# 388_Project.net
KiCad netlist of a schematic drawn in EAGLE
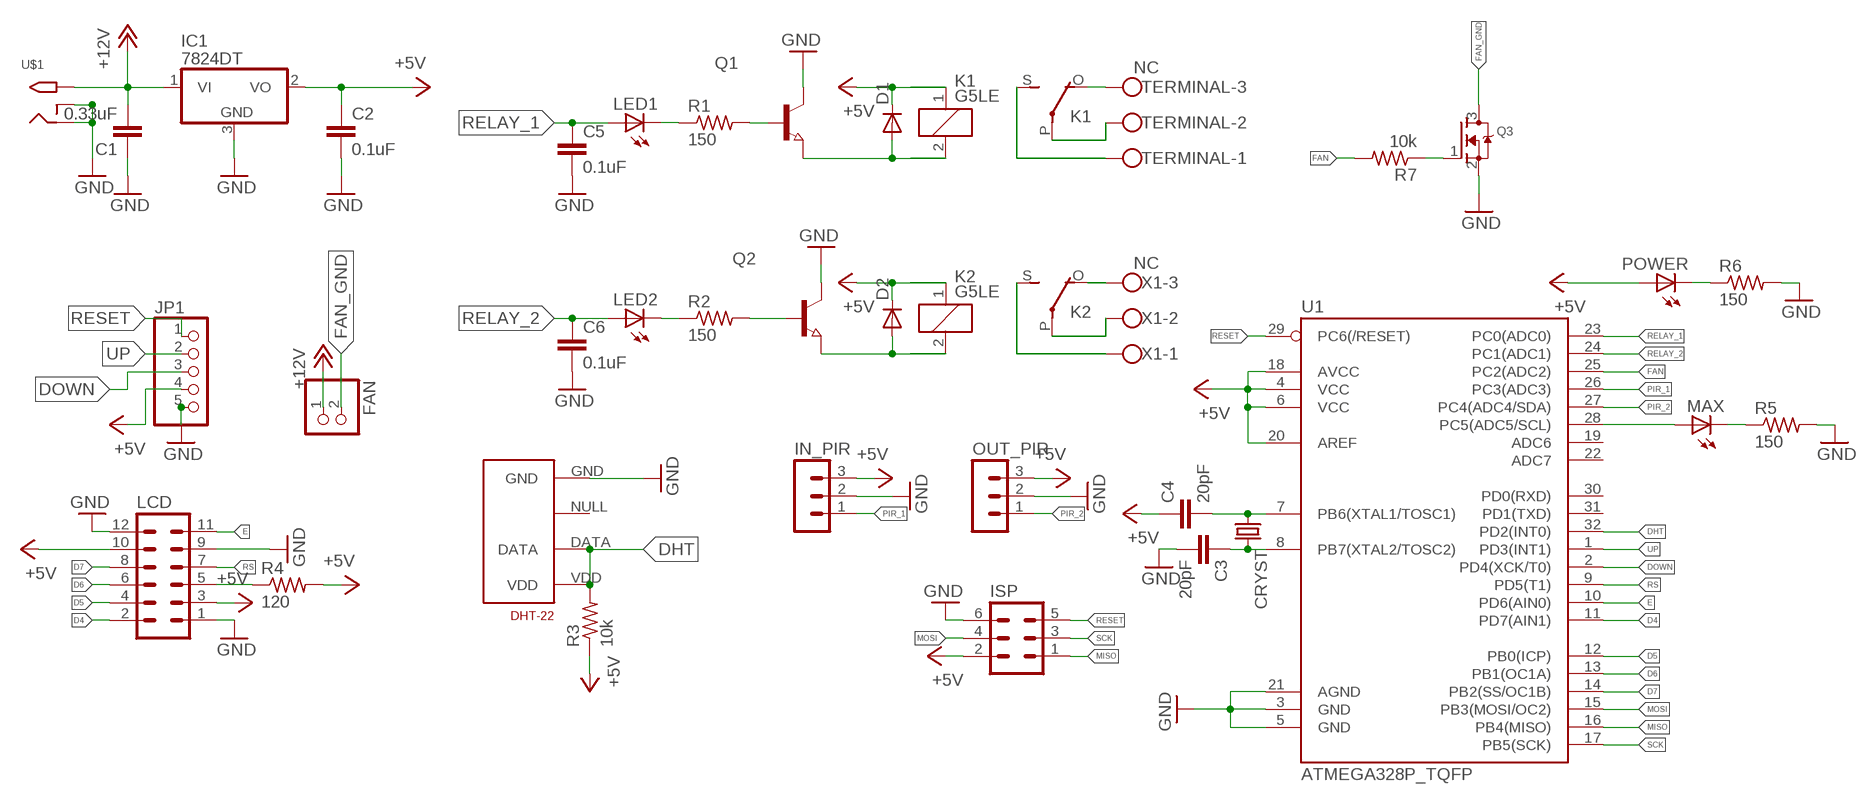
[diagram p0: schematic, sheet 1]

(export (version "E")
  (design (tool "Eeschema 10.0.6"))
  (components
    (comp (ref "C1")
      (value "0.33uF")
      (footprint "eagle-import:0805")
      (libsource (lib "eagle-import") (part "CAP0805"))
    )
    (comp (ref "C2")
      (value "0.1uF")
      (footprint "eagle-import:0805")
      (libsource (lib "eagle-import") (part "CAP0805"))
    )
    (comp (ref "C3")
      (value "20pF")
      (footprint "eagle-import:0805")
      (libsource (lib "eagle-import") (part "CAP0805"))
    )
    (comp (ref "C4")
      (value "20pF")
      (footprint "eagle-import:0805")
      (libsource (lib "eagle-import") (part "CAP0805"))
    )
    (comp (ref "C5")
      (value "0.1uF")
      (footprint "eagle-import:0805")
      (libsource (lib "eagle-import") (part "CAP0805"))
    )
    (comp (ref "C6")
      (value "0.1uF")
      (footprint "eagle-import:0805")
      (libsource (lib "eagle-import") (part "CAP0805"))
    )
    (comp (ref "CRYST")
      (value "CRYSTALHC49UP")
      (footprint "eagle-import:HC49UP")
      (libsource (lib "eagle-import") (part "CRYSTALHC49UP"))
    )
    (comp (ref "D1")
      (value "DIODE-DO-214AC")
      (footprint "eagle-import:DO-214AC")
      (libsource (lib "eagle-import") (part "DIODE-DO-214AC"))
    )
    (comp (ref "D2")
      (value "DIODE-DO-214AC")
      (footprint "eagle-import:DO-214AC")
      (libsource (lib "eagle-import") (part "DIODE-DO-214AC"))
    )
    (comp (ref "DHT-22")
      (value "RHT03_DHT-22_AM2302RA")
      (footprint "eagle-import:RHT03_DHT-22_RA")
      (libsource (lib "eagle-import") (part "RHT03_DHT-22_AM2302RA"))
    )
    (comp (ref "FAN")
      (value "JST_2PIN-SMT")
      (footprint "eagle-import:JST-PH-2-SMT")
      (libsource (lib "eagle-import") (part "JST_2PIN-SMT"))
    )
    (comp (ref "IC1")
      (value "7824DT")
      (footprint "eagle-import:TO252")
      (libsource (lib "eagle-import") (part "78DT24"))
    )
    (comp (ref "IN_PIR")
      (value "MA03-1")
      (footprint "eagle-import:MA03-1")
      (libsource (lib "eagle-import") (part "MA03-1"))
    )
    (comp (ref "ISP")
      (value "MA03-2")
      (footprint "eagle-import:MA03-2")
      (libsource (lib "eagle-import") (part "MA03-2"))
    )
    (comp (ref "JP1")
      (value "PINHD-1X5")
      (footprint "eagle-import:1X05")
      (libsource (lib "eagle-import") (part "PINHD-1X5"))
    )
    (comp (ref "K1")
      (value "G5LE")
      (footprint "eagle-import:G5LE")
      (libsource (lib "eagle-import") (part "G5LE"))
    )
    (comp (ref "K2")
      (value "G5LE")
      (footprint "eagle-import:G5LE")
      (libsource (lib "eagle-import") (part "G5LE"))
    )
    (comp (ref "LCD")
      (value "MA06-2")
      (footprint "eagle-import:MA06-2")
      (libsource (lib "eagle-import") (part "MA06-2"))
    )
    (comp (ref "LED1")
      (value "LEDSML0805")
      (footprint "eagle-import:SML0805")
      (libsource (lib "eagle-import") (part "LEDSML0805"))
    )
    (comp (ref "LED2")
      (value "LEDSML0805")
      (footprint "eagle-import:SML0805")
      (libsource (lib "eagle-import") (part "LEDSML0805"))
    )
    (comp (ref "MAX")
      (value "LEDSML0805")
      (footprint "eagle-import:SML0805")
      (libsource (lib "eagle-import") (part "LEDSML0805"))
    )
    (comp (ref "OUT_PIR")
      (value "MA03-1")
      (footprint "eagle-import:MA03-1")
      (libsource (lib "eagle-import") (part "MA03-1"))
    )
    (comp (ref "POWER")
      (value "LEDSML0805")
      (footprint "eagle-import:SML0805")
      (libsource (lib "eagle-import") (part "LEDSML0805"))
    )
    (comp (ref "Q1")
      (value "NPN-TRANSISTOR_SOT23")
      (footprint "eagle-import:SOT23")
      (libsource (lib "eagle-import") (part "NPN-TRANSISTOR_SOT23"))
    )
    (comp (ref "Q2")
      (value "NPN-TRANSISTOR_SOT23")
      (footprint "eagle-import:SOT23")
      (libsource (lib "eagle-import") (part "NPN-TRANSISTOR_SOT23"))
    )
    (comp (ref "Q3")
      (value "MOSFET-NREFLOW")
      (footprint "eagle-import:SOT23")
      (libsource (lib "eagle-import") (part "MOSFET-NREFLOW"))
    )
    (comp (ref "R1")
      (value "150")
      (footprint "eagle-import:M0805")
      (libsource (lib "eagle-import") (part "R-US_M0805"))
    )
    (comp (ref "R2")
      (value "150")
      (footprint "eagle-import:M0805")
      (libsource (lib "eagle-import") (part "R-US_M0805"))
    )
    (comp (ref "R3")
      (value "10k")
      (footprint "eagle-import:M0805")
      (libsource (lib "eagle-import") (part "R-US_M0805"))
    )
    (comp (ref "R4")
      (value "120")
      (footprint "eagle-import:M0805")
      (libsource (lib "eagle-import") (part "R-US_M0805"))
    )
    (comp (ref "R5")
      (value "150")
      (footprint "eagle-import:M0805")
      (libsource (lib "eagle-import") (part "R-US_M0805"))
    )
    (comp (ref "R6")
      (value "150")
      (footprint "eagle-import:M0805")
      (libsource (lib "eagle-import") (part "R-US_M0805"))
    )
    (comp (ref "R7")
      (value "10k")
      (footprint "eagle-import:M0805")
      (libsource (lib "eagle-import") (part "R-US_M0805"))
    )
    (comp (ref "TERMINAL")
      (value "NC")
      (footprint "eagle-import:W237-103")
      (fields (field (name "MPN") "237-103"))
      (libsource (lib "eagle-import") (part "W237-103"))
    )
    (comp (ref "U$1")
      (value "2.1MMJACKTHM")
      (footprint "eagle-import:PJ-102A")
      (libsource (lib "eagle-import") (part "2.1MMJACKTHM"))
    )
    (comp (ref "U1")
      (value "ATMEGA328P_TQFP")
      (footprint "eagle-import:TQFP32-08")
      (libsource (lib "eagle-import") (part "ATMEGA328P_TQFP"))
    )
    (comp (ref "X1")
      (value "NC")
      (footprint "eagle-import:W237-103")
      (fields (field (name "MPN") "237-103"))
      (libsource (lib "eagle-import") (part "W237-103"))
    )
  )
  (nets
    (net (code "1") (name "+5V") (class "Default")
      (node (ref "C2") (pin "1") (pinfunction "1_1") (pintype "passive"))
      (node (ref "C4") (pin "1") (pinfunction "1_1") (pintype "passive"))
      (node (ref "D1") (pin "C") (pinfunction "C_C") (pintype "passive"))
      (node (ref "D2") (pin "C") (pinfunction "C_C") (pintype "passive"))
      (node (ref "IC1") (pin "2") (pinfunction "VO_2") (pintype "passive"))
      (node (ref "IN_PIR") (pin "3") (pinfunction "3_3") (pintype "passive"))
      (node (ref "ISP") (pin "2") (pinfunction "2_2") (pintype "passive"))
      (node (ref "JP1") (pin "4") (pinfunction "4_4") (pintype "passive"))
      (node (ref "K1") (pin "1") (pinfunction "1_1") (pintype "passive"))
      (node (ref "K2") (pin "1") (pinfunction "1_1") (pintype "passive"))
      (node (ref "LCD") (pin "10") (pinfunction "10_10") (pintype "passive"))
      (node (ref "LCD") (pin "3") (pinfunction "3_3") (pintype "passive"))
      (node (ref "OUT_PIR") (pin "3") (pinfunction "3_3") (pintype "passive"))
      (node (ref "POWER") (pin "A") (pinfunction "A_A") (pintype "passive"))
      (node (ref "R3") (pin "1") (pinfunction "1_1") (pintype "passive"))
      (node (ref "R4") (pin "2") (pinfunction "2_2") (pintype "passive"))
      (node (ref "U1") (pin "18") (pinfunction "AVCC_18") (pintype "bidirectional"))
      (node (ref "U1") (pin "20") (pinfunction "AREF_20") (pintype "bidirectional"))
      (node (ref "U1") (pin "4") (pinfunction "VCC_4") (pintype "bidirectional"))
      (node (ref "U1") (pin "6") (pinfunction "VCC_6") (pintype "bidirectional"))
    )
    (net (code "2") (name "+12V") (class "Default")
      (node (ref "C1") (pin "2") (pinfunction "2_2") (pintype "passive"))
      (node (ref "FAN") (pin "1") (pinfunction "2_1") (pintype "passive"))
      (node (ref "IC1") (pin "1") (pinfunction "VI_1") (pintype "input"))
      (node (ref "U$1") (pin "TIP") (pinfunction "TIP_TIP") (pintype "bidirectional"))
    )
    (net (code "3") (name "D4") (class "Default")
      (node (ref "LCD") (pin "2") (pinfunction "2_2") (pintype "passive"))
      (node (ref "U1") (pin "11") (pinfunction "PD7(AIN1)_11") (pintype "bidirectional"))
    )
    (net (code "4") (name "D5") (class "Default")
      (node (ref "LCD") (pin "4") (pinfunction "4_4") (pintype "passive"))
      (node (ref "U1") (pin "12") (pinfunction "PB0(ICP)_12") (pintype "bidirectional"))
    )
    (net (code "5") (name "D6") (class "Default")
      (node (ref "LCD") (pin "6") (pinfunction "6_6") (pintype "passive"))
      (node (ref "U1") (pin "13") (pinfunction "PB1(OC1A)_13") (pintype "bidirectional"))
    )
    (net (code "6") (name "D7") (class "Default")
      (node (ref "LCD") (pin "8") (pinfunction "8_8") (pintype "passive"))
      (node (ref "U1") (pin "14") (pinfunction "PB2(SS/OC1B)_14") (pintype "bidirectional"))
    )
    (net (code "7") (name "DHT") (class "Default")
      (node (ref "DHT-22") (pin "DATA") (pinfunction "DATA_DATA") (pintype "bidirectional"))
      (node (ref "DHT-22") (pin "VDD") (pinfunction "VDD_VDD") (pintype "power_in"))
      (node (ref "R3") (pin "2") (pinfunction "2_2") (pintype "passive"))
      (node (ref "U1") (pin "32") (pinfunction "PD2(INT0)_32") (pintype "bidirectional"))
    )
    (net (code "8") (name "DOWN") (class "Default")
      (node (ref "JP1") (pin "3") (pinfunction "3_3") (pintype "passive"))
      (node (ref "U1") (pin "2") (pinfunction "PD4(XCK/T0)_2") (pintype "bidirectional"))
    )
    (net (code "9") (name "E") (class "Default")
      (node (ref "LCD") (pin "11") (pinfunction "11_11") (pintype "passive"))
      (node (ref "U1") (pin "10") (pinfunction "PD6(AIN0)_10") (pintype "bidirectional"))
    )
    (net (code "10") (name "FAN") (class "Default")
      (node (ref "R7") (pin "2") (pinfunction "2_2") (pintype "passive"))
      (node (ref "U1") (pin "25") (pinfunction "PC2(ADC2)_25") (pintype "bidirectional"))
    )
    (net (code "11") (name "FAN_GND") (class "Default")
      (node (ref "FAN") (pin "2") (pinfunction "1_2") (pintype "passive"))
      (node (ref "Q3") (pin "3") (pinfunction "D_3") (pintype "bidirectional"))
    )
    (net (code "12") (name "GND") (class "Default")
      (node (ref "C1") (pin "1") (pinfunction "1_1") (pintype "passive"))
      (node (ref "C2") (pin "2") (pinfunction "2_2") (pintype "passive"))
      (node (ref "C3") (pin "2") (pinfunction "2_2") (pintype "passive"))
      (node (ref "C5") (pin "2") (pinfunction "2_2") (pintype "passive"))
      (node (ref "C6") (pin "2") (pinfunction "2_2") (pintype "passive"))
      (node (ref "DHT-22") (pin "GND") (pinfunction "GND_GND") (pintype "power_in"))
      (node (ref "IC1") (pin "3") (pinfunction "GND_3") (pintype "passive"))
      (node (ref "IN_PIR") (pin "2") (pinfunction "2_2") (pintype "passive"))
      (node (ref "ISP") (pin "6") (pinfunction "6_6") (pintype "passive"))
      (node (ref "JP1") (pin "5") (pinfunction "5_5") (pintype "passive"))
      (node (ref "LCD") (pin "1") (pinfunction "1_1") (pintype "passive"))
      (node (ref "LCD") (pin "12") (pinfunction "12_12") (pintype "passive"))
      (node (ref "LCD") (pin "9") (pinfunction "9_9") (pintype "passive"))
      (node (ref "OUT_PIR") (pin "2") (pinfunction "2_2") (pintype "passive"))
      (node (ref "Q1") (pin "3") (pinfunction "C_3") (pintype "passive"))
      (node (ref "Q2") (pin "3") (pinfunction "C_3") (pintype "passive"))
      (node (ref "Q3") (pin "2") (pinfunction "S_2") (pintype "bidirectional"))
      (node (ref "R5") (pin "2") (pinfunction "2_2") (pintype "passive"))
      (node (ref "R6") (pin "2") (pinfunction "2_2") (pintype "passive"))
      (node (ref "U$1") (pin "RING") (pinfunction "RING_RING") (pintype "bidirectional"))
      (node (ref "U$1") (pin "RING_SW") (pinfunction "RING_SW_RING_SW") (pintype "bidirectional"))
      (node (ref "U1") (pin "21") (pinfunction "AGND_21") (pintype "bidirectional"))
      (node (ref "U1") (pin "3") (pinfunction "GND_3") (pintype "bidirectional"))
      (node (ref "U1") (pin "5") (pinfunction "GND_5") (pintype "bidirectional"))
    )
    (net (code "13") (name "MISO") (class "Default")
      (node (ref "ISP") (pin "1") (pinfunction "1_1") (pintype "passive"))
      (node (ref "U1") (pin "16") (pinfunction "PB4(MISO)_16") (pintype "bidirectional"))
    )
    (net (code "14") (name "MOSI") (class "Default")
      (node (ref "ISP") (pin "4") (pinfunction "4_4") (pintype "passive"))
      (node (ref "U1") (pin "15") (pinfunction "PB3(MOSI/OC2)_15") (pintype "bidirectional"))
    )
    (net (code "15") (name "Net-(LCD-Pad5)") (class "Default")
      (node (ref "LCD") (pin "5") (pinfunction "5_5") (pintype "passive"))
      (node (ref "R4") (pin "1") (pinfunction "1_1") (pintype "passive"))
    )
    (net (code "16") (name "Net-(LED1-PadC)") (class "Default")
      (node (ref "LED1") (pin "C") (pinfunction "C_C") (pintype "passive"))
      (node (ref "R1") (pin "1") (pinfunction "1_1") (pintype "passive"))
    )
    (net (code "17") (name "Net-(LED2-PadC)") (class "Default")
      (node (ref "LED2") (pin "C") (pinfunction "C_C") (pintype "passive"))
      (node (ref "R2") (pin "1") (pinfunction "1_1") (pintype "passive"))
    )
    (net (code "18") (name "Net-(MAX-PadC)") (class "Default")
      (node (ref "MAX") (pin "C") (pinfunction "C_C") (pintype "passive"))
      (node (ref "R5") (pin "1") (pinfunction "1_1") (pintype "passive"))
    )
    (net (code "19") (name "Net-(POWER-PadC)") (class "Default")
      (node (ref "POWER") (pin "C") (pinfunction "C_C") (pintype "passive"))
      (node (ref "R6") (pin "1") (pinfunction "1_1") (pintype "passive"))
    )
    (net (code "20") (name "Net-(Q1-B)") (class "Default")
      (node (ref "Q1") (pin "1") (pinfunction "B_1") (pintype "passive"))
      (node (ref "R1") (pin "2") (pinfunction "2_2") (pintype "passive"))
    )
    (net (code "21") (name "Net-(Q1-E)") (class "Default")
      (node (ref "D1") (pin "A") (pinfunction "A_A") (pintype "passive"))
      (node (ref "K1") (pin "2") (pinfunction "2_2") (pintype "passive"))
      (node (ref "Q1") (pin "2") (pinfunction "E_2") (pintype "passive"))
    )
    (net (code "22") (name "Net-(Q2-B)") (class "Default")
      (node (ref "Q2") (pin "1") (pinfunction "B_1") (pintype "passive"))
      (node (ref "R2") (pin "2") (pinfunction "2_2") (pintype "passive"))
    )
    (net (code "23") (name "Net-(Q2-E)") (class "Default")
      (node (ref "D2") (pin "A") (pinfunction "A_A") (pintype "passive"))
      (node (ref "K2") (pin "2") (pinfunction "2_2") (pintype "passive"))
      (node (ref "Q2") (pin "2") (pinfunction "E_2") (pintype "passive"))
    )
    (net (code "24") (name "Net-(Q3-G)") (class "Default")
      (node (ref "Q3") (pin "1") (pinfunction "G_1") (pintype "bidirectional"))
      (node (ref "R7") (pin "1") (pinfunction "1_1") (pintype "passive"))
    )
    (net (code "25") (name "Net-(TERMINALA-KL)") (class "Default")
      (node (ref "K1") (pin "S") (pinfunction "S_S") (pintype "passive"))
      (node (ref "TERMINAL") (pin "1") (pinfunction "KL_1") (pintype "passive"))
    )
    (net (code "26") (name "Net-(TERMINALB-KL)") (class "Default")
      (node (ref "K1") (pin "P") (pinfunction "P_P") (pintype "passive"))
      (node (ref "TERMINAL") (pin "2") (pinfunction "KL_2") (pintype "passive"))
    )
    (net (code "27") (name "Net-(TERMINALC-KL)") (class "Default")
      (node (ref "K1") (pin "O") (pinfunction "O_O") (pintype "passive"))
      (node (ref "TERMINAL") (pin "3") (pinfunction "KL_3") (pintype "passive"))
    )
    (net (code "28") (name "Net-(U1-PB6(XTAL1{slash}TOSC1))") (class "Default")
      (node (ref "C4") (pin "2") (pinfunction "2_2") (pintype "passive"))
      (node (ref "CRYST") (pin "1") (pinfunction "1_1") (pintype "passive"))
      (node (ref "U1") (pin "7") (pinfunction "PB6(XTAL1/TOSC1)_7") (pintype "bidirectional"))
    )
    (net (code "29") (name "Net-(U1-PB7(XTAL2{slash}TOSC2))") (class "Default")
      (node (ref "C3") (pin "1") (pinfunction "1_1") (pintype "passive"))
      (node (ref "CRYST") (pin "2") (pinfunction "2_2") (pintype "passive"))
      (node (ref "U1") (pin "8") (pinfunction "PB7(XTAL2/TOSC2)_8") (pintype "bidirectional"))
    )
    (net (code "30") (name "Net-(U1-PC5(ADC5{slash}SCL))") (class "Default")
      (node (ref "MAX") (pin "A") (pinfunction "A_A") (pintype "passive"))
      (node (ref "U1") (pin "28") (pinfunction "PC5(ADC5/SCL)_28") (pintype "bidirectional"))
    )
    (net (code "31") (name "Net-(X1A-KL)") (class "Default")
      (node (ref "K2") (pin "S") (pinfunction "S_S") (pintype "passive"))
      (node (ref "X1") (pin "1") (pinfunction "KL_1") (pintype "passive"))
    )
    (net (code "32") (name "Net-(X1B-KL)") (class "Default")
      (node (ref "K2") (pin "P") (pinfunction "P_P") (pintype "passive"))
      (node (ref "X1") (pin "2") (pinfunction "KL_2") (pintype "passive"))
    )
    (net (code "33") (name "Net-(X1C-KL)") (class "Default")
      (node (ref "K2") (pin "O") (pinfunction "O_O") (pintype "passive"))
      (node (ref "X1") (pin "3") (pinfunction "KL_3") (pintype "passive"))
    )
    (net (code "34") (name "PIR_1") (class "Default")
      (node (ref "IN_PIR") (pin "1") (pinfunction "1_1") (pintype "passive"))
      (node (ref "U1") (pin "26") (pinfunction "PC3(ADC3)_26") (pintype "bidirectional"))
    )
    (net (code "35") (name "PIR_2") (class "Default")
      (node (ref "OUT_PIR") (pin "1") (pinfunction "1_1") (pintype "passive"))
      (node (ref "U1") (pin "27") (pinfunction "PC4(ADC4/SDA)_27") (pintype "bidirectional"))
    )
    (net (code "36") (name "RELAY_1") (class "Default")
      (node (ref "C5") (pin "1") (pinfunction "1_1") (pintype "passive"))
      (node (ref "LED1") (pin "A") (pinfunction "A_A") (pintype "passive"))
      (node (ref "U1") (pin "23") (pinfunction "PC0(ADC0)_23") (pintype "bidirectional"))
    )
    (net (code "37") (name "RELAY_2") (class "Default")
      (node (ref "C6") (pin "1") (pinfunction "1_1") (pintype "passive"))
      (node (ref "LED2") (pin "A") (pinfunction "A_A") (pintype "passive"))
      (node (ref "U1") (pin "24") (pinfunction "PC1(ADC1)_24") (pintype "bidirectional"))
    )
    (net (code "38") (name "RESET") (class "Default")
      (node (ref "ISP") (pin "5") (pinfunction "5_5") (pintype "passive"))
      (node (ref "JP1") (pin "1") (pinfunction "1_1") (pintype "passive"))
      (node (ref "U1") (pin "29") (pinfunction "PC6(/RESET)_29") (pintype "bidirectional"))
    )
    (net (code "39") (name "RS") (class "Default")
      (node (ref "LCD") (pin "7") (pinfunction "7_7") (pintype "passive"))
      (node (ref "U1") (pin "9") (pinfunction "PD5(T1)_9") (pintype "bidirectional"))
    )
    (net (code "40") (name "SCK") (class "Default")
      (node (ref "ISP") (pin "3") (pinfunction "3_3") (pintype "passive"))
      (node (ref "U1") (pin "17") (pinfunction "PB5(SCK)_17") (pintype "bidirectional"))
    )
    (net (code "41") (name "UP") (class "Default")
      (node (ref "JP1") (pin "2") (pinfunction "2_2") (pintype "passive"))
      (node (ref "U1") (pin "1") (pinfunction "PD3(INT1)_1") (pintype "bidirectional"))
    )
    (net (code "42") (name "unconnected-(DHT-22-PadNULL)") (class "Default")
      (node (ref "DHT-22") (pin "NULL") (pinfunction "NULL_NULL") (pintype "no_connect"))
    )
    (net (code "43") (name "unconnected-(U1-ADC6-Pad19)") (class "Default")
      (node (ref "U1") (pin "19") (pinfunction "ADC6_19") (pintype "bidirectional"))
    )
    (net (code "44") (name "unconnected-(U1-ADC7-Pad22)") (class "Default")
      (node (ref "U1") (pin "22") (pinfunction "ADC7_22") (pintype "bidirectional"))
    )
    (net (code "45") (name "unconnected-(U1-PD0(RXD)-Pad30)") (class "Default")
      (node (ref "U1") (pin "30") (pinfunction "PD0(RXD)_30") (pintype "bidirectional"))
    )
    (net (code "46") (name "unconnected-(U1-PD1(TXD)-Pad31)") (class "Default")
      (node (ref "U1") (pin "31") (pinfunction "PD1(TXD)_31") (pintype "bidirectional"))
    )
  )
)
